# Tag.net
KiCad netlist of a schematic drawn in Altium Designer
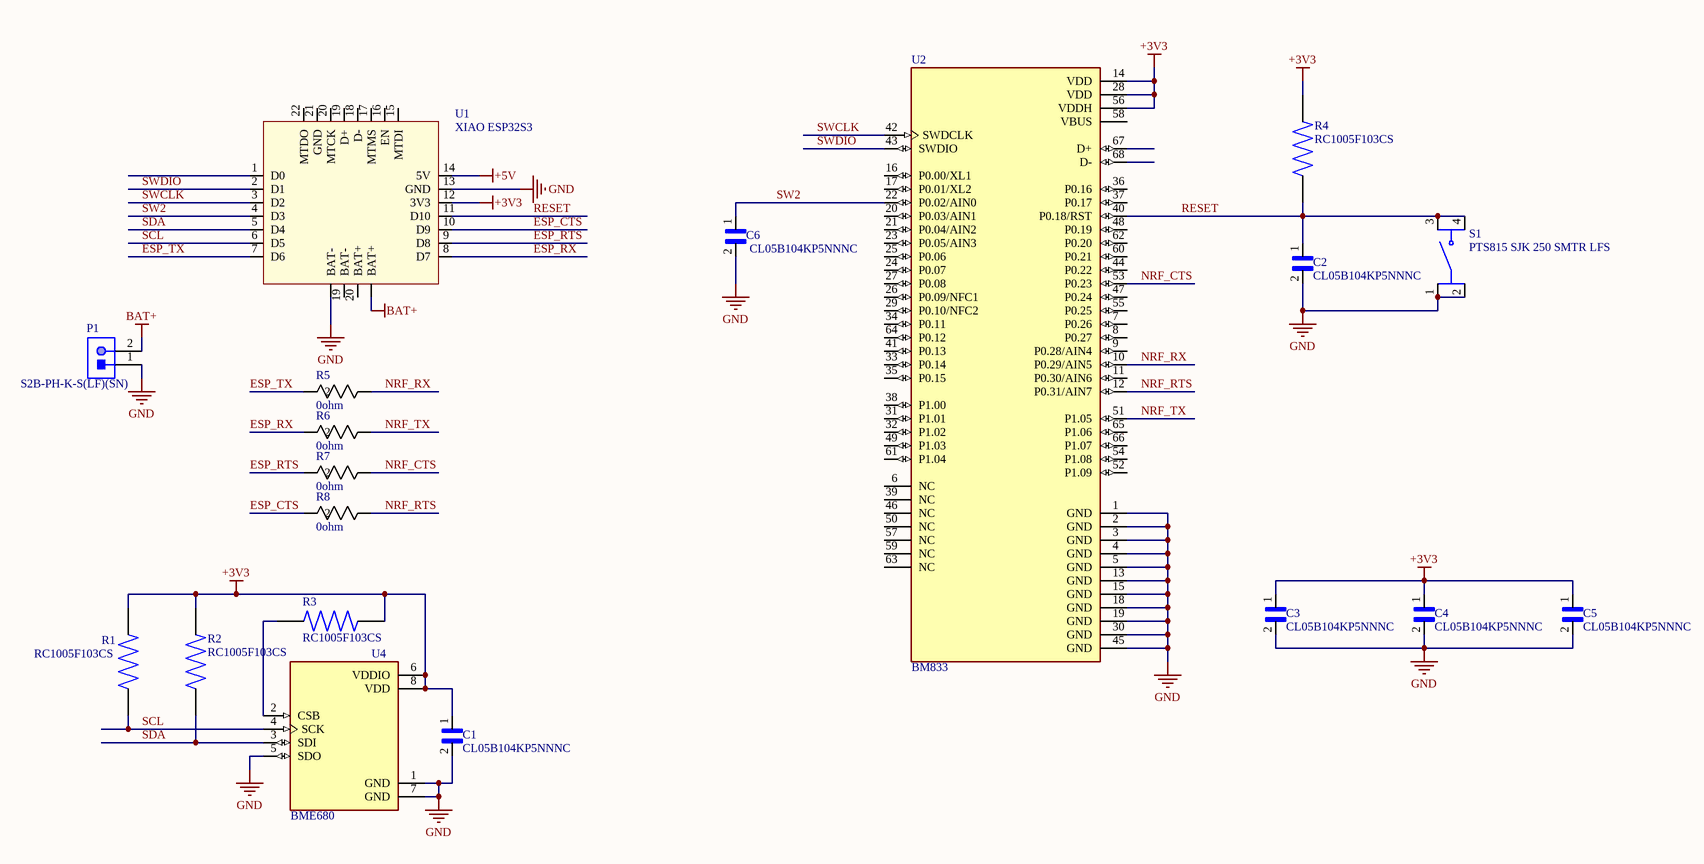
[diagram p0: Tag.SchDoc]

(export (version "E")
  (design (tool "Eeschema 10.0.6"))
  (components
    (comp (ref "C1")
      (value "CL05B104KP5NNNC")
      (footprint "CAPC1005X55N")
      (description "0.1ÂµF Â±10% 10V Ceramic Capacitor X7R 0402 _1005 Metric_")
      (fields (field (name "MF") "Samsung Electro-Mechanics"))
      (libsource (lib "CL05B104KP5NNNC") (part "CL05B104KP5NNNC"))
    )
    (comp (ref "C2")
      (value "CL05B104KP5NNNC")
      (footprint "CAPC1005X55N")
      (description "0.1ÂµF Â±10% 10V Ceramic Capacitor X7R 0402 _1005 Metric_")
      (fields (field (name "MF") "Samsung Electro-Mechanics"))
      (libsource (lib "CL05B104KP5NNNC") (part "CL05B104KP5NNNC"))
    )
    (comp (ref "C3")
      (value "CL05B104KP5NNNC")
      (footprint "CAPC1005X55N")
      (description "0.1ÂµF Â±10% 10V Ceramic Capacitor X7R 0402 _1005 Metric_")
      (fields (field (name "MF") "Samsung Electro-Mechanics"))
      (libsource (lib "CL05B104KP5NNNC") (part "CL05B104KP5NNNC"))
    )
    (comp (ref "C4")
      (value "CL05B104KP5NNNC")
      (footprint "CAPC1005X55N")
      (description "0.1ÂµF Â±10% 10V Ceramic Capacitor X7R 0402 _1005 Metric_")
      (fields (field (name "MF") "Samsung Electro-Mechanics"))
      (libsource (lib "CL05B104KP5NNNC") (part "CL05B104KP5NNNC"))
    )
    (comp (ref "C5")
      (value "CL05B104KP5NNNC")
      (footprint "CAPC1005X55N")
      (description "0.1ÂµF Â±10% 10V Ceramic Capacitor X7R 0402 _1005 Metric_")
      (fields (field (name "MF") "Samsung Electro-Mechanics"))
      (libsource (lib "CL05B104KP5NNNC") (part "CL05B104KP5NNNC"))
    )
    (comp (ref "C6")
      (value "CL05B104KP5NNNC")
      (footprint "CAPC1005X55N")
      (description "0.1ÂµF Â±10% 10V Ceramic Capacitor X7R 0402 _1005 Metric_")
      (fields (field (name "MF") "Samsung Electro-Mechanics"))
      (libsource (lib "CL05B104KP5NNNC") (part "CL05B104KP5NNNC"))
    )
    (comp (ref "P1")
      (value "S2B-PH-K-S(LF)(SN)")
      (footprint "JST-S2B-PH-K-S_V")
      (fields (field (name "TOLERANCE") "20%"))
      (libsource (lib "SchLib1") (part "CMP-1755-00004-1"))
    )
    (comp (ref "R1")
      (value "RC1005F103CS")
      (footprint "RESC1005X40N")
      (description "10 kOhms Â±1% 0.063W, 1/16W Chip Resistor 0402 (1005 Metric) Moisture Resistant Thick Film")
      (fields (field (name "MF") "Samsung Electro-Mechanics"))
      (libsource (lib "RC1005F103CS") (part "RC1005F103CS"))
    )
    (comp (ref "R2")
      (value "RC1005F103CS")
      (footprint "RESC1005X40N")
      (description "10 kOhms Â±1% 0.063W, 1/16W Chip Resistor 0402 (1005 Metric) Moisture Resistant Thick Film")
      (fields (field (name "MF") "Samsung Electro-Mechanics"))
      (libsource (lib "RC1005F103CS") (part "RC1005F103CS"))
    )
    (comp (ref "R3")
      (value "RC1005F103CS")
      (footprint "RESC1005X40N")
      (description "10 kOhms Â±1% 0.063W, 1/16W Chip Resistor 0402 (1005 Metric) Moisture Resistant Thick Film")
      (fields (field (name "MF") "Samsung Electro-Mechanics"))
      (libsource (lib "RC1005F103CS") (part "RC1005F103CS"))
    )
    (comp (ref "R4")
      (value "RC1005F103CS")
      (footprint "RESC1005X40N")
      (description "10 kOhms Â±1% 0.063W, 1/16W Chip Resistor 0402 (1005 Metric) Moisture Resistant Thick Film")
      (fields (field (name "MF") "Samsung Electro-Mechanics"))
      (libsource (lib "RC1005F103CS") (part "RC1005F103CS"))
    )
    (comp (ref "R5")
      (value "0ohm")
      (footprint "RC0402N_YAG")
      (description "No Description Available")
      (libsource (lib "SchLib1") (part "RC0402JR-070RL"))
    )
    (comp (ref "R6")
      (value "0ohm")
      (footprint "RC0402N_YAG")
      (description "No Description Available")
      (libsource (lib "SchLib1") (part "RC0402JR-070RL"))
    )
    (comp (ref "R7")
      (value "0ohm")
      (footprint "RC0402N_YAG")
      (description "No Description Available")
      (libsource (lib "SchLib1") (part "RC0402JR-070RL"))
    )
    (comp (ref "R8")
      (value "0ohm")
      (footprint "RC0402N_YAG")
      (description "No Description Available")
      (libsource (lib "SchLib1") (part "RC0402JR-070RL"))
    )
    (comp (ref "S1")
      (value "PTS815 SJK 250 SMTR LFS")
      (footprint "SWITCH_SMTR LFS")
      (description "No Description Available")
      (libsource (lib "SchLib1") (part "PTS815 SJK 250 SMTR LFS"))
    )
    (comp (ref "U1")
      (value "XIAO ESP32S3")
      (footprint "XIAO_ESP32S3")
      (libsource (lib "SchLib1") (part "XIAO_ESP32S3"))
    )
    (comp (ref "U2")
      (value "BM833")
      (footprint "XCVR_BM833")
      (description "802.15.4, Bluetooth Bluetooth v5.1 Transceiver Module 2.4GHz PCB Trace Surface Mount")
      (fields (field (name "MF") "Fanstel"))
      (libsource (lib "SchLib1") (part "BM833"))
    )
    (comp (ref "U4")
      (value "BME680")
      (footprint "PSON80P300X300X100-8N")
      (description "Gas, Humidity, Pressure, Temperature Sensor IÂ²C, SPI Output")
      (fields (field (name "MF") "Bosch Sensortec"))
      (libsource (lib "BME680") (part "BME680"))
    )
  )
  (nets
    (net (code "1") (name "+3V3") (class "Default")
      (node (ref "C1") (pin "1") (pinfunction "1_1") (pintype "passive"))
      (node (ref "C3") (pin "1") (pinfunction "1_1") (pintype "passive"))
      (node (ref "C4") (pin "1") (pinfunction "1_1") (pintype "passive"))
      (node (ref "C5") (pin "1") (pinfunction "1_1") (pintype "passive"))
      (node (ref "R1") (pin "2") (pinfunction "2_2") (pintype "passive"))
      (node (ref "R2") (pin "2") (pinfunction "2_2") (pintype "passive"))
      (node (ref "R3") (pin "1") (pinfunction "1_1") (pintype "passive"))
      (node (ref "R4") (pin "1") (pinfunction "1_1") (pintype "passive"))
      (node (ref "U1") (pin "12") (pinfunction "3V3_12") (pintype "passive"))
      (node (ref "U2") (pin "14") (pinfunction "VDD_14") (pintype "power_in"))
      (node (ref "U2") (pin "28") (pinfunction "VDD_28") (pintype "power_in"))
      (node (ref "U2") (pin "56") (pinfunction "VDDH_56") (pintype "power_in"))
      (node (ref "U4") (pin "6") (pinfunction "VDDIO_6") (pintype "power_in"))
      (node (ref "U4") (pin "8") (pinfunction "VDD_8") (pintype "power_in"))
    )
    (net (code "2") (name "+5V") (class "Default")
      (node (ref "U1") (pin "14") (pinfunction "5V_14") (pintype "passive"))
    )
    (net (code "3") (name "/ESP_CTS") (class "Default")
      (node (ref "R8") (pin "2") (pinfunction "2_2") (pintype "passive"))
      (node (ref "U1") (pin "10") (pinfunction "D9_10") (pintype "passive"))
    )
    (net (code "4") (name "/ESP_RTS") (class "Default")
      (node (ref "R7") (pin "2") (pinfunction "2_2") (pintype "passive"))
      (node (ref "U1") (pin "9") (pinfunction "D8_9") (pintype "passive"))
    )
    (net (code "5") (name "/ESP_RX") (class "Default")
      (node (ref "R6") (pin "2") (pinfunction "2_2") (pintype "passive"))
      (node (ref "U1") (pin "8") (pinfunction "D7_8") (pintype "passive"))
    )
    (net (code "6") (name "/ESP_TX") (class "Default")
      (node (ref "R5") (pin "2") (pinfunction "2_2") (pintype "passive"))
      (node (ref "U1") (pin "7") (pinfunction "D6_7") (pintype "passive"))
    )
    (net (code "7") (name "/NRF_CTS") (class "Default")
      (node (ref "R7") (pin "1") (pinfunction "1_1") (pintype "passive"))
      (node (ref "U2") (pin "53") (pinfunction "P0.23_53") (pintype "bidirectional"))
    )
    (net (code "8") (name "/NRF_RTS") (class "Default")
      (node (ref "R8") (pin "1") (pinfunction "1_1") (pintype "passive"))
      (node (ref "U2") (pin "12") (pinfunction "P0.31/AIN7_12") (pintype "bidirectional"))
    )
    (net (code "9") (name "/NRF_RX") (class "Default")
      (node (ref "R5") (pin "1") (pinfunction "1_1") (pintype "passive"))
      (node (ref "U2") (pin "10") (pinfunction "P0.29/AIN5_10") (pintype "bidirectional"))
    )
    (net (code "10") (name "/NRF_TX") (class "Default")
      (node (ref "R6") (pin "1") (pinfunction "1_1") (pintype "passive"))
      (node (ref "U2") (pin "51") (pinfunction "P1.05_51") (pintype "bidirectional"))
    )
    (net (code "11") (name "/RESET") (class "Default")
      (node (ref "C2") (pin "1") (pinfunction "1_1") (pintype "passive"))
      (node (ref "R4") (pin "2") (pinfunction "2_2") (pintype "passive"))
      (node (ref "S1") (pin "3") (pinfunction "3_3") (pintype "passive"))
      (node (ref "S1") (pin "4") (pinfunction "4_4") (pintype "passive"))
      (node (ref "U1") (pin "11") (pinfunction "D10_11") (pintype "passive"))
      (node (ref "U2") (pin "40") (pinfunction "P0.18/RST_40") (pintype "bidirectional"))
    )
    (net (code "12") (name "/SCL") (class "Default")
      (node (ref "R1") (pin "1") (pinfunction "1_1") (pintype "passive"))
      (node (ref "U1") (pin "6") (pinfunction "D5_6") (pintype "passive"))
      (node (ref "U4") (pin "4") (pinfunction "SCK_4") (pintype "input"))
    )
    (net (code "13") (name "/SDA") (class "Default")
      (node (ref "R2") (pin "1") (pinfunction "1_1") (pintype "passive"))
      (node (ref "U1") (pin "5") (pinfunction "D4_5") (pintype "passive"))
      (node (ref "U4") (pin "3") (pinfunction "SDI_3") (pintype "bidirectional"))
    )
    (net (code "14") (name "/SW2") (class "Default")
      (node (ref "C6") (pin "1") (pinfunction "1_1") (pintype "passive"))
      (node (ref "U1") (pin "4") (pinfunction "D3_4") (pintype "passive"))
      (node (ref "U2") (pin "22") (pinfunction "P0.02/AIN0_22") (pintype "bidirectional"))
    )
    (net (code "15") (name "/SWCLK") (class "Default")
      (node (ref "U1") (pin "3") (pinfunction "D2_3") (pintype "passive"))
      (node (ref "U2") (pin "42") (pinfunction "SWDCLK_42") (pintype "input"))
    )
    (net (code "16") (name "/SWDIO") (class "Default")
      (node (ref "U1") (pin "2") (pinfunction "D1_2") (pintype "passive"))
      (node (ref "U2") (pin "43") (pinfunction "SWDIO_43") (pintype "bidirectional"))
    )
    (net (code "17") (name "BAT+") (class "Default")
      (node (ref "P1") (pin "2") (pinfunction "2_2") (pintype "passive"))
      (node (ref "U1") (pin "BAT+") (pinfunction "BAT+_BAT+") (pintype "passive"))
    )
    (net (code "18") (name "GND") (class "Default")
      (node (ref "C1") (pin "2") (pinfunction "2_2") (pintype "passive"))
      (node (ref "C2") (pin "2") (pinfunction "2_2") (pintype "passive"))
      (node (ref "C3") (pin "2") (pinfunction "2_2") (pintype "passive"))
      (node (ref "C4") (pin "2") (pinfunction "2_2") (pintype "passive"))
      (node (ref "C5") (pin "2") (pinfunction "2_2") (pintype "passive"))
      (node (ref "C6") (pin "2") (pinfunction "2_2") (pintype "passive"))
      (node (ref "P1") (pin "1") (pinfunction "1_1") (pintype "passive"))
      (node (ref "S1") (pin "1") (pinfunction "1_1") (pintype "passive"))
      (node (ref "S1") (pin "2") (pinfunction "2_2") (pintype "passive"))
      (node (ref "U1") (pin "13") (pinfunction "GND_13") (pintype "passive"))
      (node (ref "U1") (pin "BAT-") (pinfunction "BAT-_BAT-") (pintype "passive"))
      (node (ref "U2") (pin "1") (pinfunction "GND_1") (pintype "power_in"))
      (node (ref "U2") (pin "13") (pinfunction "GND_13") (pintype "power_in"))
      (node (ref "U2") (pin "15") (pinfunction "GND_15") (pintype "power_in"))
      (node (ref "U2") (pin "18") (pinfunction "GND_18") (pintype "power_in"))
      (node (ref "U2") (pin "19") (pinfunction "GND_19") (pintype "power_in"))
      (node (ref "U2") (pin "2") (pinfunction "GND_2") (pintype "power_in"))
      (node (ref "U2") (pin "3") (pinfunction "GND_3") (pintype "power_in"))
      (node (ref "U2") (pin "30") (pinfunction "GND_30") (pintype "power_in"))
      (node (ref "U2") (pin "4") (pinfunction "GND_4") (pintype "power_in"))
      (node (ref "U2") (pin "45") (pinfunction "GND_45") (pintype "power_in"))
      (node (ref "U2") (pin "5") (pinfunction "GND_5") (pintype "power_in"))
      (node (ref "U4") (pin "1") (pinfunction "GND_1") (pintype "power_in"))
      (node (ref "U4") (pin "5") (pinfunction "SDO_5") (pintype "bidirectional"))
      (node (ref "U4") (pin "7") (pinfunction "GND_7") (pintype "power_in"))
    )
    (net (code "19") (name "Net-(U4-CSB)") (class "Default")
      (node (ref "R3") (pin "2") (pinfunction "2_2") (pintype "passive"))
      (node (ref "U4") (pin "2") (pinfunction "CSB_2") (pintype "input"))
    )
    (net (code "20") (name "unconnected-(U1-BAT+-Pad20)") (class "Default")
      (node (ref "U1") (pin "20") (pinfunction "BAT+_20") (pintype "passive"))
    )
    (net (code "21") (name "unconnected-(U1-BAT--Pad19)") (class "Default")
      (node (ref "U1") (pin "19") (pinfunction "BAT-_19") (pintype "passive"))
    )
    (net (code "22") (name "unconnected-(U1-D+-Pad19)") (class "Default")
      (node (ref "U1") (pin "19") (pinfunction "D+_19") (pintype "passive"))
    )
    (net (code "23") (name "unconnected-(U1-D--Pad18)") (class "Default")
      (node (ref "U1") (pin "18") (pinfunction "D-_18") (pintype "passive"))
    )
    (net (code "24") (name "unconnected-(U1-D0-Pad1)") (class "Default")
      (node (ref "U1") (pin "1") (pinfunction "D0_1") (pintype "passive"))
    )
    (net (code "25") (name "unconnected-(U1-EN-Pad16)") (class "Default")
      (node (ref "U1") (pin "16") (pinfunction "EN_16") (pintype "passive"))
    )
    (net (code "26") (name "unconnected-(U1-GND-Pad21)") (class "Default")
      (node (ref "U1") (pin "21") (pinfunction "GND_21") (pintype "passive"))
    )
    (net (code "27") (name "unconnected-(U1-MTCK-Pad20)") (class "Default")
      (node (ref "U1") (pin "20") (pinfunction "MTCK_20") (pintype "passive"))
    )
    (net (code "28") (name "unconnected-(U1-MTDI-Pad15)") (class "Default")
      (node (ref "U1") (pin "15") (pinfunction "MTDI_15") (pintype "passive"))
    )
    (net (code "29") (name "unconnected-(U1-MTDO-Pad22)") (class "Default")
      (node (ref "U1") (pin "22") (pinfunction "MTDO_22") (pintype "passive"))
    )
    (net (code "30") (name "unconnected-(U1-MTMS-Pad17)") (class "Default")
      (node (ref "U1") (pin "17") (pinfunction "MTMS_17") (pintype "passive"))
    )
    (net (code "31") (name "unconnected-(U2-D+-Pad67)") (class "Default")
      (node (ref "U2") (pin "67") (pinfunction "D+_67") (pintype "bidirectional"))
    )
    (net (code "32") (name "unconnected-(U2-D--Pad68)") (class "Default")
      (node (ref "U2") (pin "68") (pinfunction "D-_68") (pintype "bidirectional"))
    )
    (net (code "33") (name "unconnected-(U2-NC-Pad6)") (class "Default")
      (node (ref "U2") (pin "6") (pinfunction "NC_6") (pintype "passive"))
    )
    (net (code "34") (name "unconnected-(U2-NC-Pad39)") (class "Default")
      (node (ref "U2") (pin "39") (pinfunction "NC_39") (pintype "passive"))
    )
    (net (code "35") (name "unconnected-(U2-NC-Pad46)") (class "Default")
      (node (ref "U2") (pin "46") (pinfunction "NC_46") (pintype "passive"))
    )
    (net (code "36") (name "unconnected-(U2-NC-Pad50)") (class "Default")
      (node (ref "U2") (pin "50") (pinfunction "NC_50") (pintype "passive"))
    )
    (net (code "37") (name "unconnected-(U2-NC-Pad57)") (class "Default")
      (node (ref "U2") (pin "57") (pinfunction "NC_57") (pintype "passive"))
    )
    (net (code "38") (name "unconnected-(U2-NC-Pad59)") (class "Default")
      (node (ref "U2") (pin "59") (pinfunction "NC_59") (pintype "passive"))
    )
    (net (code "39") (name "unconnected-(U2-NC-Pad63)") (class "Default")
      (node (ref "U2") (pin "63") (pinfunction "NC_63") (pintype "passive"))
    )
    (net (code "40") (name "unconnected-(U2-P0.00{slash}XL1-Pad16)") (class "Default")
      (node (ref "U2") (pin "16") (pinfunction "P0.00/XL1_16") (pintype "bidirectional"))
    )
    (net (code "41") (name "unconnected-(U2-P0.01{slash}XL2-Pad17)") (class "Default")
      (node (ref "U2") (pin "17") (pinfunction "P0.01/XL2_17") (pintype "bidirectional"))
    )
    (net (code "42") (name "unconnected-(U2-P0.03{slash}AIN1-Pad20)") (class "Default")
      (node (ref "U2") (pin "20") (pinfunction "P0.03/AIN1_20") (pintype "bidirectional"))
    )
    (net (code "43") (name "unconnected-(U2-P0.04{slash}AIN2-Pad21)") (class "Default")
      (node (ref "U2") (pin "21") (pinfunction "P0.04/AIN2_21") (pintype "bidirectional"))
    )
    (net (code "44") (name "unconnected-(U2-P0.05{slash}AIN3-Pad23)") (class "Default")
      (node (ref "U2") (pin "23") (pinfunction "P0.05/AIN3_23") (pintype "bidirectional"))
    )
    (net (code "45") (name "unconnected-(U2-P0.06-Pad25)") (class "Default")
      (node (ref "U2") (pin "25") (pinfunction "P0.06_25") (pintype "bidirectional"))
    )
    (net (code "46") (name "unconnected-(U2-P0.07-Pad24)") (class "Default")
      (node (ref "U2") (pin "24") (pinfunction "P0.07_24") (pintype "bidirectional"))
    )
    (net (code "47") (name "unconnected-(U2-P0.08-Pad27)") (class "Default")
      (node (ref "U2") (pin "27") (pinfunction "P0.08_27") (pintype "bidirectional"))
    )
    (net (code "48") (name "unconnected-(U2-P0.09{slash}NFC1-Pad26)") (class "Default")
      (node (ref "U2") (pin "26") (pinfunction "P0.09/NFC1_26") (pintype "bidirectional"))
    )
    (net (code "49") (name "unconnected-(U2-P0.10{slash}NFC2-Pad29)") (class "Default")
      (node (ref "U2") (pin "29") (pinfunction "P0.10/NFC2_29") (pintype "bidirectional"))
    )
    (net (code "50") (name "unconnected-(U2-P0.11-Pad34)") (class "Default")
      (node (ref "U2") (pin "34") (pinfunction "P0.11_34") (pintype "bidirectional"))
    )
    (net (code "51") (name "unconnected-(U2-P0.12-Pad64)") (class "Default")
      (node (ref "U2") (pin "64") (pinfunction "P0.12_64") (pintype "bidirectional"))
    )
    (net (code "52") (name "unconnected-(U2-P0.13-Pad41)") (class "Default")
      (node (ref "U2") (pin "41") (pinfunction "P0.13_41") (pintype "bidirectional"))
    )
    (net (code "53") (name "unconnected-(U2-P0.14-Pad33)") (class "Default")
      (node (ref "U2") (pin "33") (pinfunction "P0.14_33") (pintype "bidirectional"))
    )
    (net (code "54") (name "unconnected-(U2-P0.15-Pad35)") (class "Default")
      (node (ref "U2") (pin "35") (pinfunction "P0.15_35") (pintype "bidirectional"))
    )
    (net (code "55") (name "unconnected-(U2-P0.16-Pad36)") (class "Default")
      (node (ref "U2") (pin "36") (pinfunction "P0.16_36") (pintype "bidirectional"))
    )
    (net (code "56") (name "unconnected-(U2-P0.17-Pad37)") (class "Default")
      (node (ref "U2") (pin "37") (pinfunction "P0.17_37") (pintype "bidirectional"))
    )
    (net (code "57") (name "unconnected-(U2-P0.19-Pad48)") (class "Default")
      (node (ref "U2") (pin "48") (pinfunction "P0.19_48") (pintype "bidirectional"))
    )
    (net (code "58") (name "unconnected-(U2-P0.20-Pad62)") (class "Default")
      (node (ref "U2") (pin "62") (pinfunction "P0.20_62") (pintype "bidirectional"))
    )
    (net (code "59") (name "unconnected-(U2-P0.21-Pad60)") (class "Default")
      (node (ref "U2") (pin "60") (pinfunction "P0.21_60") (pintype "bidirectional"))
    )
    (net (code "60") (name "unconnected-(U2-P0.22-Pad44)") (class "Default")
      (node (ref "U2") (pin "44") (pinfunction "P0.22_44") (pintype "bidirectional"))
    )
    (net (code "61") (name "unconnected-(U2-P0.24-Pad47)") (class "Default")
      (node (ref "U2") (pin "47") (pinfunction "P0.24_47") (pintype "bidirectional"))
    )
    (net (code "62") (name "unconnected-(U2-P0.25-Pad55)") (class "Default")
      (node (ref "U2") (pin "55") (pinfunction "P0.25_55") (pintype "bidirectional"))
    )
    (net (code "63") (name "unconnected-(U2-P0.26-Pad7)") (class "Default")
      (node (ref "U2") (pin "7") (pinfunction "P0.26_7") (pintype "bidirectional"))
    )
    (net (code "64") (name "unconnected-(U2-P0.27-Pad8)") (class "Default")
      (node (ref "U2") (pin "8") (pinfunction "P0.27_8") (pintype "bidirectional"))
    )
    (net (code "65") (name "unconnected-(U2-P0.28{slash}AIN4-Pad9)") (class "Default")
      (node (ref "U2") (pin "9") (pinfunction "P0.28/AIN4_9") (pintype "bidirectional"))
    )
    (net (code "66") (name "unconnected-(U2-P0.30{slash}AIN6-Pad11)") (class "Default")
      (node (ref "U2") (pin "11") (pinfunction "P0.30/AIN6_11") (pintype "bidirectional"))
    )
    (net (code "67") (name "unconnected-(U2-P1.00-Pad38)") (class "Default")
      (node (ref "U2") (pin "38") (pinfunction "P1.00_38") (pintype "bidirectional"))
    )
    (net (code "68") (name "unconnected-(U2-P1.01-Pad31)") (class "Default")
      (node (ref "U2") (pin "31") (pinfunction "P1.01_31") (pintype "bidirectional"))
    )
    (net (code "69") (name "unconnected-(U2-P1.02-Pad32)") (class "Default")
      (node (ref "U2") (pin "32") (pinfunction "P1.02_32") (pintype "bidirectional"))
    )
    (net (code "70") (name "unconnected-(U2-P1.03-Pad49)") (class "Default")
      (node (ref "U2") (pin "49") (pinfunction "P1.03_49") (pintype "bidirectional"))
    )
    (net (code "71") (name "unconnected-(U2-P1.04-Pad61)") (class "Default")
      (node (ref "U2") (pin "61") (pinfunction "P1.04_61") (pintype "bidirectional"))
    )
    (net (code "72") (name "unconnected-(U2-P1.06-Pad65)") (class "Default")
      (node (ref "U2") (pin "65") (pinfunction "P1.06_65") (pintype "bidirectional"))
    )
    (net (code "73") (name "unconnected-(U2-P1.07-Pad66)") (class "Default")
      (node (ref "U2") (pin "66") (pinfunction "P1.07_66") (pintype "bidirectional"))
    )
    (net (code "74") (name "unconnected-(U2-P1.08-Pad54)") (class "Default")
      (node (ref "U2") (pin "54") (pinfunction "P1.08_54") (pintype "bidirectional"))
    )
    (net (code "75") (name "unconnected-(U2-P1.09-Pad52)") (class "Default")
      (node (ref "U2") (pin "52") (pinfunction "P1.09_52") (pintype "bidirectional"))
    )
    (net (code "76") (name "unconnected-(U2-VBUS-Pad58)") (class "Default")
      (node (ref "U2") (pin "58") (pinfunction "VBUS_58") (pintype "power_in"))
    )
  )
)
